# LEDs.net
KiCad netlist of a schematic drawn in Altium Designer
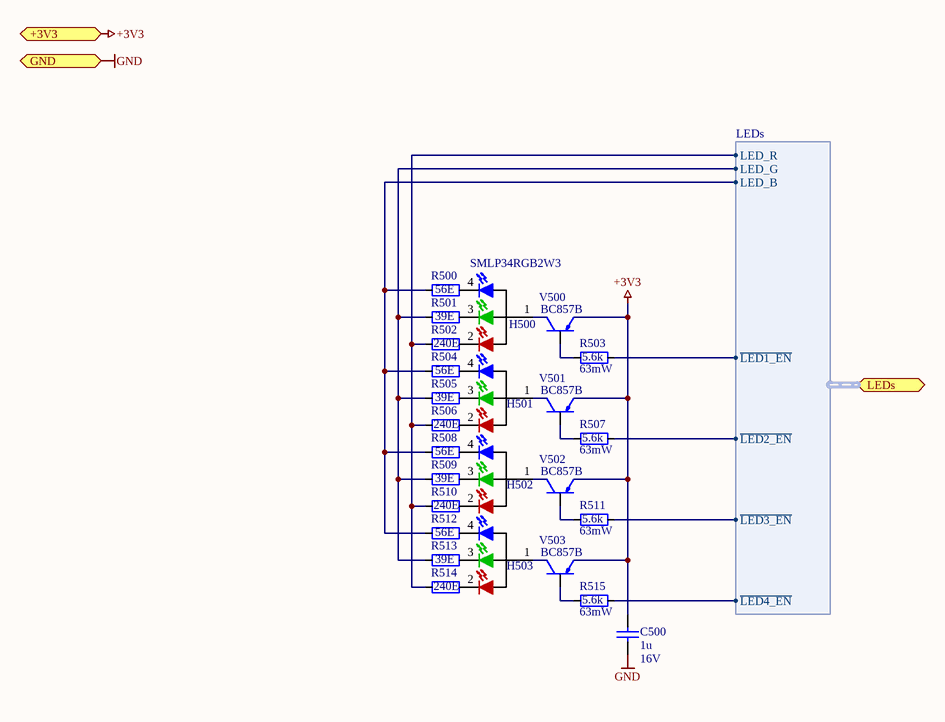
[diagram p0: LEDs.SchDoc]

(export (version "E")
  (design (tool "Eeschema 10.0.6"))
  (components
    (comp (ref "C500")
      (value "1u")
      (footprint "SMD_CAP_0603")
      (description "1µF ±10% 16V Ceramic Capacitor X7R 0603 (1608 Metric)")
      (fields (field (name "VALUE2") "16V") (field (name "Comment") "C_SMD_CER_1U_16V_10%_X7R_0603"))
      (libsource (lib "AM") (part "C_SMD_CER_1U_16V_10%_X7R_0603"))
    )
    (comp (ref "H500")
      (value "H_SMD_LED_RGB_DIFFUSED_5MA_0404")
      (footprint "SMD_LED_0404")
      (fields (field (name "TYPE") "SMLP34RGB2W3"))
      (libsource (lib "AM") (part "H_SMD_LED_RGB_DIFFUSED_5MA_0404"))
    )
    (comp (ref "H501")
      (value "H_SMD_LED_RGB_DIFFUSED_5MA_0404")
      (footprint "SMD_LED_0404")
      (libsource (lib "AM") (part "H_SMD_LED_RGB_DIFFUSED_5MA_0404"))
    )
    (comp (ref "H502")
      (value "H_SMD_LED_RGB_DIFFUSED_5MA_0404")
      (footprint "SMD_LED_0404")
      (libsource (lib "AM") (part "H_SMD_LED_RGB_DIFFUSED_5MA_0404"))
    )
    (comp (ref "H503")
      (value "H_SMD_LED_RGB_DIFFUSED_5MA_0404")
      (footprint "SMD_LED_0404")
      (libsource (lib "AM") (part "H_SMD_LED_RGB_DIFFUSED_5MA_0404"))
    )
    (comp (ref "R500")
      (value "56E")
      (footprint "SMD_RES_0402")
      (description "56 Ohms ±0.5% 0.063W, 1/16W Chip Resistor 0402 (1005 Metric) Thin Film")
      (fields (field (name "Comment") "R_SMD_THINFILM_56E_0W063_0%5_50PPM_0402"))
      (libsource (lib "AM") (part "R_SMD_THINFILM_56E_0W063_0%5_50PPM_0402"))
    )
    (comp (ref "R501")
      (value "39E")
      (footprint "SMD_RES_0402")
      (description "39 Ohms ±0.5% 0.063W, 1/16W Chip Resistor 0402 (1005 Metric) Thin Film")
      (fields (field (name "Comment") "R_SMD_THINFILM_39E_0W063_0%5_50PPM_0402"))
      (libsource (lib "AM") (part "R_SMD_THINFILM_39E_0W063_0%5_50PPM_0402"))
    )
    (comp (ref "R502")
      (value "240E")
      (footprint "SMD_RES_0402")
      (description "240 Ohms ±0.5% 0.063W, 1/16W Chip Resistor 0402 (1005 Metric) Automotive AEC-Q200 Thin Film")
      (fields (field (name "Comment") "R_SMD_THINFILM_240E_0W063_0%5_25PPM_0402"))
      (libsource (lib "AM") (part "R_SMD_THINFILM_240E_0W063_0%5_25PPM_0402"))
    )
    (comp (ref "R503")
      (value "5.6k")
      (footprint "SMD_RES_0402")
      (description "5.6 kOhms ±0.5% 0.063W, 1/16W Chip Resistor 0402 (1005 Metric) Automotive AEC-Q200 Thin Film")
      (fields
        (field (name "VALUE2") "63mW")
        (field (name "Comment") "R_SMD_THINFILM_5K6_0W063_0%5_25PPM_0402")
      )
      (libsource (lib "AM") (part "R_SMD_THINFILM_5K6_0W063_0%5_25PPM_0402"))
    )
    (comp (ref "R504")
      (value "56E")
      (footprint "SMD_RES_0402")
      (description "56 Ohms ±0.5% 0.063W, 1/16W Chip Resistor 0402 (1005 Metric) Thin Film")
      (fields (field (name "Comment") "R_SMD_THINFILM_56E_0W063_0%5_50PPM_0402"))
      (libsource (lib "AM") (part "R_SMD_THINFILM_56E_0W063_0%5_50PPM_0402"))
    )
    (comp (ref "R505")
      (value "39E")
      (footprint "SMD_RES_0402")
      (description "39 Ohms ±0.5% 0.063W, 1/16W Chip Resistor 0402 (1005 Metric) Thin Film")
      (fields (field (name "Comment") "R_SMD_THINFILM_39E_0W063_0%5_50PPM_0402"))
      (libsource (lib "AM") (part "R_SMD_THINFILM_39E_0W063_0%5_50PPM_0402"))
    )
    (comp (ref "R506")
      (value "240E")
      (footprint "SMD_RES_0402")
      (description "240 Ohms ±0.5% 0.063W, 1/16W Chip Resistor 0402 (1005 Metric) Automotive AEC-Q200 Thin Film")
      (fields (field (name "Comment") "R_SMD_THINFILM_240E_0W063_0%5_25PPM_0402"))
      (libsource (lib "AM") (part "R_SMD_THINFILM_240E_0W063_0%5_25PPM_0402"))
    )
    (comp (ref "R507")
      (value "5.6k")
      (footprint "SMD_RES_0402")
      (description "5.6 kOhms ±0.5% 0.063W, 1/16W Chip Resistor 0402 (1005 Metric) Automotive AEC-Q200 Thin Film")
      (fields
        (field (name "VALUE2") "63mW")
        (field (name "Comment") "R_SMD_THINFILM_5K6_0W063_0%5_25PPM_0402")
      )
      (libsource (lib "AM") (part "R_SMD_THINFILM_5K6_0W063_0%5_25PPM_0402"))
    )
    (comp (ref "R508")
      (value "56E")
      (footprint "SMD_RES_0402")
      (description "56 Ohms ±0.5% 0.063W, 1/16W Chip Resistor 0402 (1005 Metric) Thin Film")
      (fields (field (name "Comment") "R_SMD_THINFILM_56E_0W063_0%5_50PPM_0402"))
      (libsource (lib "AM") (part "R_SMD_THINFILM_56E_0W063_0%5_50PPM_0402"))
    )
    (comp (ref "R509")
      (value "39E")
      (footprint "SMD_RES_0402")
      (description "39 Ohms ±0.5% 0.063W, 1/16W Chip Resistor 0402 (1005 Metric) Thin Film")
      (fields (field (name "Comment") "R_SMD_THINFILM_39E_0W063_0%5_50PPM_0402"))
      (libsource (lib "AM") (part "R_SMD_THINFILM_39E_0W063_0%5_50PPM_0402"))
    )
    (comp (ref "R510")
      (value "240E")
      (footprint "SMD_RES_0402")
      (description "240 Ohms ±0.5% 0.063W, 1/16W Chip Resistor 0402 (1005 Metric) Automotive AEC-Q200 Thin Film")
      (fields (field (name "Comment") "R_SMD_THINFILM_240E_0W063_0%5_25PPM_0402"))
      (libsource (lib "AM") (part "R_SMD_THINFILM_240E_0W063_0%5_25PPM_0402"))
    )
    (comp (ref "R511")
      (value "5.6k")
      (footprint "SMD_RES_0402")
      (description "5.6 kOhms ±0.5% 0.063W, 1/16W Chip Resistor 0402 (1005 Metric) Automotive AEC-Q200 Thin Film")
      (fields
        (field (name "VALUE2") "63mW")
        (field (name "Comment") "R_SMD_THINFILM_5K6_0W063_0%5_25PPM_0402")
      )
      (libsource (lib "AM") (part "R_SMD_THINFILM_5K6_0W063_0%5_25PPM_0402"))
    )
    (comp (ref "R512")
      (value "56E")
      (footprint "SMD_RES_0402")
      (description "56 Ohms ±0.5% 0.063W, 1/16W Chip Resistor 0402 (1005 Metric) Thin Film")
      (fields (field (name "Comment") "R_SMD_THINFILM_56E_0W063_0%5_50PPM_0402"))
      (libsource (lib "AM") (part "R_SMD_THINFILM_56E_0W063_0%5_50PPM_0402"))
    )
    (comp (ref "R513")
      (value "39E")
      (footprint "SMD_RES_0402")
      (description "39 Ohms ±0.5% 0.063W, 1/16W Chip Resistor 0402 (1005 Metric) Thin Film")
      (fields (field (name "Comment") "R_SMD_THINFILM_39E_0W063_0%5_50PPM_0402"))
      (libsource (lib "AM") (part "R_SMD_THINFILM_39E_0W063_0%5_50PPM_0402"))
    )
    (comp (ref "R514")
      (value "240E")
      (footprint "SMD_RES_0402")
      (description "240 Ohms ±0.5% 0.063W, 1/16W Chip Resistor 0402 (1005 Metric) Automotive AEC-Q200 Thin Film")
      (fields (field (name "Comment") "R_SMD_THINFILM_240E_0W063_0%5_25PPM_0402"))
      (libsource (lib "AM") (part "R_SMD_THINFILM_240E_0W063_0%5_25PPM_0402"))
    )
    (comp (ref "R515")
      (value "5.6k")
      (footprint "SMD_RES_0402")
      (description "5.6 kOhms ±0.5% 0.063W, 1/16W Chip Resistor 0402 (1005 Metric) Automotive AEC-Q200 Thin Film")
      (fields
        (field (name "VALUE2") "63mW")
        (field (name "Comment") "R_SMD_THINFILM_5K6_0W063_0%5_25PPM_0402")
      )
      (libsource (lib "AM") (part "R_SMD_THINFILM_5K6_0W063_0%5_25PPM_0402"))
    )
    (comp (ref "V500")
      (value "V_SMD_TRANS_PNP_BC857B_45V_0A1_SOT-23-3")
      (footprint "SMD_SOT_23_3")
      (description "SMD PNP Transistor BC857B 100mA 45V")
      (fields (field (name "TYPE") "BC857B"))
      (libsource (lib "AM") (part "V_SMD_TRANS_PNP_BC857B_45V_0A1_SOT-23-3"))
    )
    (comp (ref "V501")
      (value "V_SMD_TRANS_PNP_BC857B_45V_0A1_SOT-23-3")
      (footprint "SMD_SOT_23_3")
      (description "SMD PNP Transistor BC857B 100mA 45V")
      (fields (field (name "TYPE") "BC857B"))
      (libsource (lib "AM") (part "V_SMD_TRANS_PNP_BC857B_45V_0A1_SOT-23-3"))
    )
    (comp (ref "V502")
      (value "V_SMD_TRANS_PNP_BC857B_45V_0A1_SOT-23-3")
      (footprint "SMD_SOT_23_3")
      (description "SMD PNP Transistor BC857B 100mA 45V")
      (fields (field (name "TYPE") "BC857B"))
      (libsource (lib "AM") (part "V_SMD_TRANS_PNP_BC857B_45V_0A1_SOT-23-3"))
    )
    (comp (ref "V503")
      (value "V_SMD_TRANS_PNP_BC857B_45V_0A1_SOT-23-3")
      (footprint "SMD_SOT_23_3")
      (description "SMD PNP Transistor BC857B 100mA 45V")
      (fields (field (name "TYPE") "BC857B"))
      (libsource (lib "AM") (part "V_SMD_TRANS_PNP_BC857B_45V_0A1_SOT-23-3"))
    )
  )
  (nets
    (net (code "2") (name "+3V3") (class "Default")
      (node (ref "C500") (pin "2") (pinfunction "2_2") (pintype "passive"))
      (node (ref "V500") (pin "2") (pinfunction "E_2") (pintype "passive"))
      (node (ref "V501") (pin "2") (pinfunction "E_2") (pintype "passive"))
      (node (ref "V502") (pin "2") (pinfunction "E_2") (pintype "passive"))
      (node (ref "V503") (pin "2") (pinfunction "E_2") (pintype "passive"))
    )
    (net (code "3") (name "/LED_B") (class "Default")
      (node (ref "R500") (pin "1") (pinfunction "1_1") (pintype "passive"))
      (node (ref "R504") (pin "1") (pinfunction "1_1") (pintype "passive"))
      (node (ref "R508") (pin "1") (pinfunction "1_1") (pintype "passive"))
      (node (ref "R512") (pin "1") (pinfunction "1_1") (pintype "passive"))
    )
    (net (code "4") (name "/LED_G") (class "Default")
      (node (ref "R501") (pin "1") (pinfunction "1_1") (pintype "passive"))
      (node (ref "R505") (pin "1") (pinfunction "1_1") (pintype "passive"))
      (node (ref "R509") (pin "1") (pinfunction "1_1") (pintype "passive"))
      (node (ref "R513") (pin "1") (pinfunction "1_1") (pintype "passive"))
    )
    (net (code "5") (name "/LED_R") (class "Default")
      (node (ref "R502") (pin "1") (pinfunction "1_1") (pintype "passive"))
      (node (ref "R506") (pin "1") (pinfunction "1_1") (pintype "passive"))
      (node (ref "R510") (pin "1") (pinfunction "1_1") (pintype "passive"))
      (node (ref "R514") (pin "1") (pinfunction "1_1") (pintype "passive"))
    )
    (net (code "7") (name "/~{LED1_EN}") (class "Default")
      (node (ref "R503") (pin "2") (pinfunction "2_2") (pintype "passive"))
    )
    (net (code "8") (name "/~{LED2_EN}") (class "Default")
      (node (ref "R507") (pin "2") (pinfunction "2_2") (pintype "passive"))
    )
    (net (code "9") (name "/~{LED3_EN}") (class "Default")
      (node (ref "R511") (pin "2") (pinfunction "2_2") (pintype "passive"))
    )
    (net (code "10") (name "/~{LED4_EN}") (class "Default")
      (node (ref "R515") (pin "2") (pinfunction "2_2") (pintype "passive"))
    )
    (net (code "11") (name "GND") (class "Default")
      (node (ref "C500") (pin "1") (pinfunction "1_1") (pintype "passive"))
    )
    (net (code "12") (name "Net-(H500-Pad2)") (class "Default")
      (node (ref "H500") (pin "2") (pinfunction "2_2") (pintype "passive"))
      (node (ref "R502") (pin "2") (pinfunction "2_2") (pintype "passive"))
    )
    (net (code "13") (name "Net-(H500-Pad3)") (class "Default")
      (node (ref "H500") (pin "3") (pinfunction "3_3") (pintype "passive"))
      (node (ref "R501") (pin "2") (pinfunction "2_2") (pintype "passive"))
    )
    (net (code "14") (name "Net-(H500-Pad4)") (class "Default")
      (node (ref "H500") (pin "4") (pinfunction "4_4") (pintype "passive"))
      (node (ref "R500") (pin "2") (pinfunction "2_2") (pintype "passive"))
    )
    (net (code "15") (name "Net-(H501-Pad2)") (class "Default")
      (node (ref "H501") (pin "2") (pinfunction "2_2") (pintype "passive"))
      (node (ref "R506") (pin "2") (pinfunction "2_2") (pintype "passive"))
    )
    (net (code "16") (name "Net-(H501-Pad3)") (class "Default")
      (node (ref "H501") (pin "3") (pinfunction "3_3") (pintype "passive"))
      (node (ref "R505") (pin "2") (pinfunction "2_2") (pintype "passive"))
    )
    (net (code "17") (name "Net-(H501-Pad4)") (class "Default")
      (node (ref "H501") (pin "4") (pinfunction "4_4") (pintype "passive"))
      (node (ref "R504") (pin "2") (pinfunction "2_2") (pintype "passive"))
    )
    (net (code "18") (name "Net-(H502-Pad2)") (class "Default")
      (node (ref "H502") (pin "2") (pinfunction "2_2") (pintype "passive"))
      (node (ref "R510") (pin "2") (pinfunction "2_2") (pintype "passive"))
    )
    (net (code "19") (name "Net-(H502-Pad3)") (class "Default")
      (node (ref "H502") (pin "3") (pinfunction "3_3") (pintype "passive"))
      (node (ref "R509") (pin "2") (pinfunction "2_2") (pintype "passive"))
    )
    (net (code "20") (name "Net-(H502-Pad4)") (class "Default")
      (node (ref "H502") (pin "4") (pinfunction "4_4") (pintype "passive"))
      (node (ref "R508") (pin "2") (pinfunction "2_2") (pintype "passive"))
    )
    (net (code "21") (name "Net-(H503-Pad2)") (class "Default")
      (node (ref "H503") (pin "2") (pinfunction "2_2") (pintype "passive"))
      (node (ref "R514") (pin "2") (pinfunction "2_2") (pintype "passive"))
    )
    (net (code "22") (name "Net-(H503-Pad3)") (class "Default")
      (node (ref "H503") (pin "3") (pinfunction "3_3") (pintype "passive"))
      (node (ref "R513") (pin "2") (pinfunction "2_2") (pintype "passive"))
    )
    (net (code "23") (name "Net-(H503-Pad4)") (class "Default")
      (node (ref "H503") (pin "4") (pinfunction "4_4") (pintype "passive"))
      (node (ref "R512") (pin "2") (pinfunction "2_2") (pintype "passive"))
    )
    (net (code "24") (name "Net-(V500-B)") (class "Default")
      (node (ref "R503") (pin "1") (pinfunction "1_1") (pintype "passive"))
      (node (ref "V500") (pin "1") (pinfunction "B_1") (pintype "passive"))
    )
    (net (code "25") (name "Net-(V500-C)") (class "Default")
      (node (ref "H500") (pin "1") (pinfunction "1_1") (pintype "passive"))
      (node (ref "V500") (pin "3") (pinfunction "C_3") (pintype "passive"))
    )
    (net (code "26") (name "Net-(V501-B)") (class "Default")
      (node (ref "R507") (pin "1") (pinfunction "1_1") (pintype "passive"))
      (node (ref "V501") (pin "1") (pinfunction "B_1") (pintype "passive"))
    )
    (net (code "27") (name "Net-(V501-C)") (class "Default")
      (node (ref "H501") (pin "1") (pinfunction "1_1") (pintype "passive"))
      (node (ref "V501") (pin "3") (pinfunction "C_3") (pintype "passive"))
    )
    (net (code "28") (name "Net-(V502-B)") (class "Default")
      (node (ref "R511") (pin "1") (pinfunction "1_1") (pintype "passive"))
      (node (ref "V502") (pin "1") (pinfunction "B_1") (pintype "passive"))
    )
    (net (code "29") (name "Net-(V502-C)") (class "Default")
      (node (ref "H502") (pin "1") (pinfunction "1_1") (pintype "passive"))
      (node (ref "V502") (pin "3") (pinfunction "C_3") (pintype "passive"))
    )
    (net (code "30") (name "Net-(V503-B)") (class "Default")
      (node (ref "R515") (pin "1") (pinfunction "1_1") (pintype "passive"))
      (node (ref "V503") (pin "1") (pinfunction "B_1") (pintype "passive"))
    )
    (net (code "31") (name "Net-(V503-C)") (class "Default")
      (node (ref "H503") (pin "1") (pinfunction "1_1") (pintype "passive"))
      (node (ref "V503") (pin "3") (pinfunction "C_3") (pintype "passive"))
    )
  )
)
